# ADC.net
KiCad netlist of a schematic drawn in Altium Designer
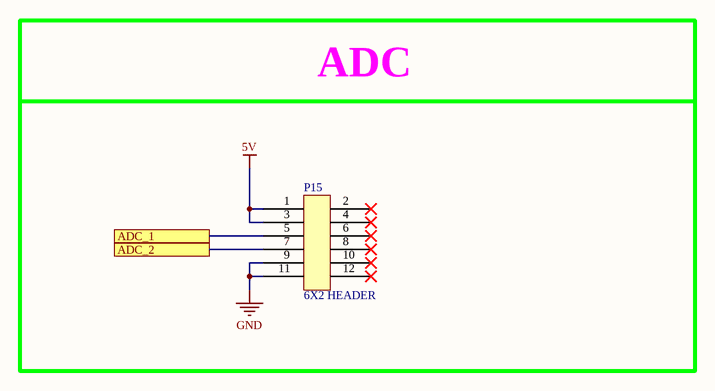
[diagram p0: ADC.SchDoc]

(export (version "E")
  (design (tool "Eeschema 10.0.6"))
  (components
    (comp (ref "P15")
      (value "CONN HEADER VERT 12POS 2.54MM")
      (footprint "281739-6")
      (description "Conn Shrouded Header HDR 12 POS 2.54mm Solder ST Thru-Hole Loose Piece")
      (fields
        (field (name "MANUFACTURER") "TE Connectivity")
        (field (name "MANUFACTURER PART NUMBER") "281739-6")
      )
      (libsource (lib "Schlib1") (part "281739-6"))
    )
  )
  (nets
    (net (code "1") (name "/ADC_1") (class "Default") (node (ref "P15") (pin "5") (pintype "passive")))
    (net (code "2") (name "/ADC_2") (class "Default") (node (ref "P15") (pin "7") (pintype "passive")))
    (net (code "3") (name "5V") (class "Default")
      (node (ref "P15") (pin "1") (pintype "passive"))
      (node (ref "P15") (pin "3") (pintype "passive"))
    )
    (net (code "4") (name "GND") (class "Default")
      (node (ref "P15") (pin "11") (pintype "passive"))
      (node (ref "P15") (pin "9") (pintype "passive"))
    )
    (net (code "5") (name "unconnected-(P15-Pad2)") (class "Default")
      (node (ref "P15") (pin "2") (pintype "passive+no_connect"))
    )
    (net (code "6") (name "unconnected-(P15-Pad4)") (class "Default")
      (node (ref "P15") (pin "4") (pintype "passive+no_connect"))
    )
    (net (code "7") (name "unconnected-(P15-Pad6)") (class "Default")
      (node (ref "P15") (pin "6") (pintype "passive+no_connect"))
    )
    (net (code "8") (name "unconnected-(P15-Pad8)") (class "Default")
      (node (ref "P15") (pin "8") (pintype "passive+no_connect"))
    )
    (net (code "9") (name "unconnected-(P15-Pad10)") (class "Default")
      (node (ref "P15") (pin "10") (pintype "passive+no_connect"))
    )
    (net (code "10") (name "unconnected-(P15-Pad12)") (class "Default")
      (node (ref "P15") (pin "12") (pintype "passive+no_connect"))
    )
  )
)
